# ir_board.net
KiCad netlist of a schematic drawn in EAGLE
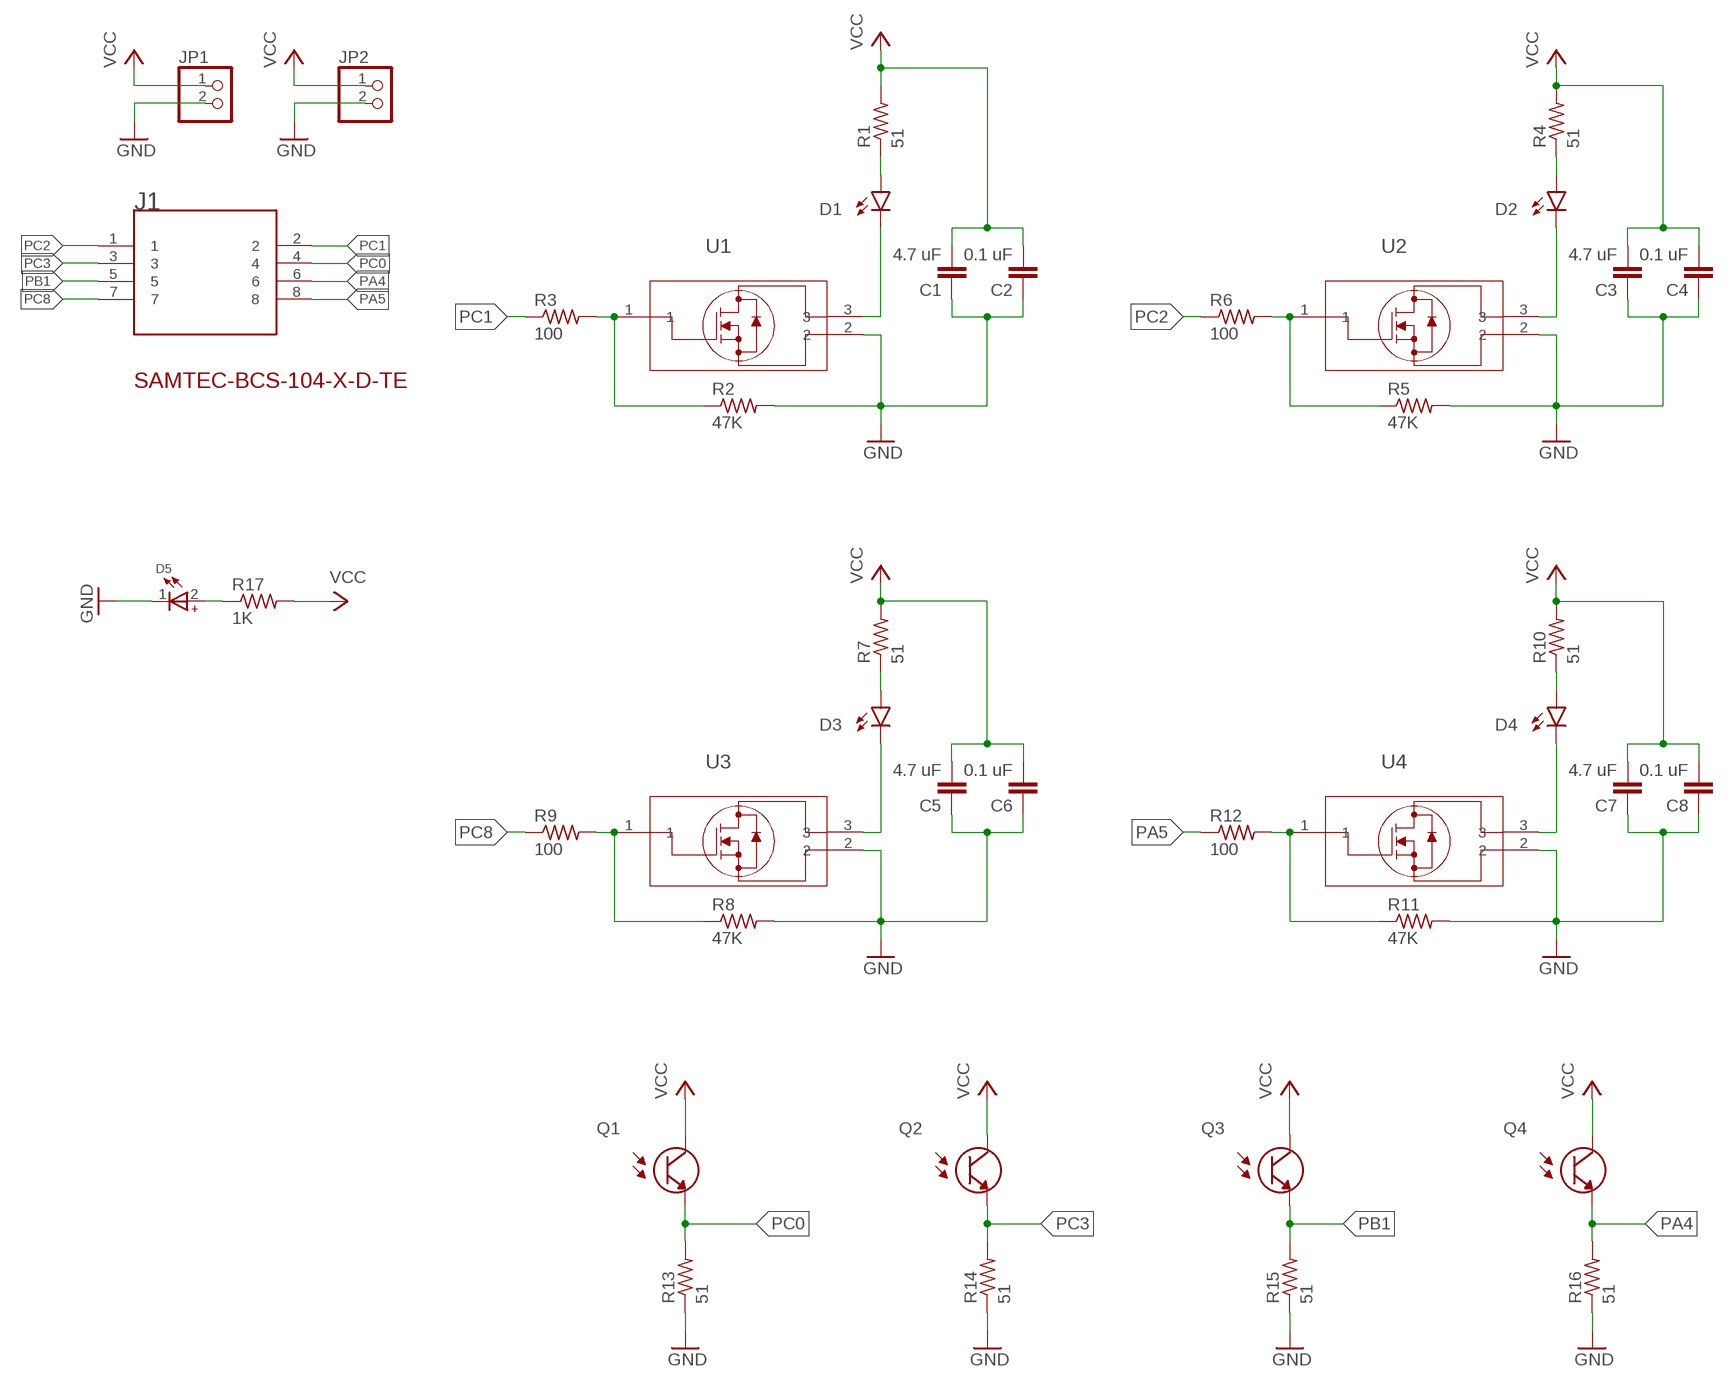
[diagram p0: schematic, sheet 1]

(export (version "E")
  (design (tool "Eeschema 10.0.6"))
  (components
    (comp (ref "C1")
      (value "4.7 uF")
      (footprint "eagle-import:C0805")
      (libsource (lib "eagle-import") (part "C-EUC0805"))
    )
    (comp (ref "C2")
      (value "0.1 uF")
      (footprint "eagle-import:C0805")
      (libsource (lib "eagle-import") (part "C-EUC0805"))
    )
    (comp (ref "C3")
      (value "4.7 uF")
      (footprint "eagle-import:C0805")
      (libsource (lib "eagle-import") (part "C-EUC0805"))
    )
    (comp (ref "C4")
      (value "0.1 uF")
      (footprint "eagle-import:C0805")
      (libsource (lib "eagle-import") (part "C-EUC0805"))
    )
    (comp (ref "C5")
      (value "4.7 uF")
      (footprint "eagle-import:C0805")
      (libsource (lib "eagle-import") (part "C-EUC0805"))
    )
    (comp (ref "C6")
      (value "0.1 uF")
      (footprint "eagle-import:C0805")
      (libsource (lib "eagle-import") (part "C-EUC0805"))
    )
    (comp (ref "C7")
      (value "4.7 uF")
      (footprint "eagle-import:C0805")
      (libsource (lib "eagle-import") (part "C-EUC0805"))
    )
    (comp (ref "C8")
      (value "0.1 uF")
      (footprint "eagle-import:C0805")
      (libsource (lib "eagle-import") (part "C-EUC0805"))
    )
    (comp (ref "D1")
      (value "LED5MM")
      (footprint "eagle-import:LED5MM")
      (libsource (lib "eagle-import") (part "LED5MM"))
    )
    (comp (ref "D2")
      (value "LED5MM")
      (footprint "eagle-import:LED5MM")
      (libsource (lib "eagle-import") (part "LED5MM"))
    )
    (comp (ref "D3")
      (value "LED5MM")
      (footprint "eagle-import:LED5MM")
      (libsource (lib "eagle-import") (part "LED5MM"))
    )
    (comp (ref "D4")
      (value "LED5MM")
      (footprint "eagle-import:LED5MM")
      (libsource (lib "eagle-import") (part "LED5MM"))
    )
    (comp (ref "D5")
      (value "WL-SMCW_0805_150080BS75000")
      (footprint "eagle-import:WL-SMCW_0805")
      (libsource (lib "eagle-import") (part "WL-SMCW_0805_150080BS75000"))
    )
    (comp (ref "J1")
      (value "SAMTEC-BCS-104-X-D-TEJ")
      (footprint "eagle-import:SAMTEC-BCS-104-X-D-TE")
      (fields (field (name "MF") "Samtec") (field (name "MP") "BCS-104-LM-D-TE"))
      (libsource (lib "eagle-import") (part "SAMTEC-BCS-104-X-D-TEJ"))
    )
    (comp (ref "JP1")
      (value "PINHD-1X2")
      (footprint "eagle-import:1X02")
      (libsource (lib "eagle-import") (part "PINHD-1X2"))
    )
    (comp (ref "JP2")
      (value "PINHD-1X2")
      (footprint "eagle-import:1X02")
      (libsource (lib "eagle-import") (part "PINHD-1X2"))
    )
    (comp (ref "Q1")
      (value "SFH_313_FA-3/4")
      (footprint "eagle-import:XDCR_SFH_313_FA-3_4")
      (fields (field (name "MF") "OSRAM Opto") (field (name "MP") "SFH 313 FA-3/4"))
      (libsource (lib "eagle-import") (part "SFH_313_FA-3/4"))
    )
    (comp (ref "Q2")
      (value "SFH_313_FA-3/4")
      (footprint "eagle-import:XDCR_SFH_313_FA-3_4")
      (fields (field (name "MF") "OSRAM Opto") (field (name "MP") "SFH 313 FA-3/4"))
      (libsource (lib "eagle-import") (part "SFH_313_FA-3/4"))
    )
    (comp (ref "Q3")
      (value "SFH_313_FA-3/4")
      (footprint "eagle-import:XDCR_SFH_313_FA-3_4")
      (fields (field (name "MF") "OSRAM Opto") (field (name "MP") "SFH 313 FA-3/4"))
      (libsource (lib "eagle-import") (part "SFH_313_FA-3/4"))
    )
    (comp (ref "Q4")
      (value "SFH_313_FA-3/4")
      (footprint "eagle-import:XDCR_SFH_313_FA-3_4")
      (fields (field (name "MF") "OSRAM Opto") (field (name "MP") "SFH 313 FA-3/4"))
      (libsource (lib "eagle-import") (part "SFH_313_FA-3/4"))
    )
    (comp (ref "R1")
      (value "51")
      (footprint "eagle-import:R0805")
      (libsource (lib "eagle-import") (part "R-US_R0805"))
    )
    (comp (ref "R2")
      (value "47K")
      (footprint "eagle-import:R0805")
      (libsource (lib "eagle-import") (part "R-US_R0805"))
    )
    (comp (ref "R3")
      (value "100")
      (footprint "eagle-import:R0805")
      (libsource (lib "eagle-import") (part "R-US_R0805"))
    )
    (comp (ref "R4")
      (value "51")
      (footprint "eagle-import:R0805")
      (libsource (lib "eagle-import") (part "R-US_R0805"))
    )
    (comp (ref "R5")
      (value "47K")
      (footprint "eagle-import:R0805")
      (libsource (lib "eagle-import") (part "R-US_R0805"))
    )
    (comp (ref "R6")
      (value "100")
      (footprint "eagle-import:R0805")
      (libsource (lib "eagle-import") (part "R-US_R0805"))
    )
    (comp (ref "R7")
      (value "51")
      (footprint "eagle-import:R0805")
      (libsource (lib "eagle-import") (part "R-US_R0805"))
    )
    (comp (ref "R8")
      (value "47K")
      (footprint "eagle-import:R0805")
      (libsource (lib "eagle-import") (part "R-US_R0805"))
    )
    (comp (ref "R9")
      (value "100")
      (footprint "eagle-import:R0805")
      (libsource (lib "eagle-import") (part "R-US_R0805"))
    )
    (comp (ref "R10")
      (value "51")
      (footprint "eagle-import:R0805")
      (libsource (lib "eagle-import") (part "R-US_R0805"))
    )
    (comp (ref "R11")
      (value "47K")
      (footprint "eagle-import:R0805")
      (libsource (lib "eagle-import") (part "R-US_R0805"))
    )
    (comp (ref "R12")
      (value "100")
      (footprint "eagle-import:R0805")
      (libsource (lib "eagle-import") (part "R-US_R0805"))
    )
    (comp (ref "R13")
      (value "51")
      (footprint "eagle-import:R0805")
      (libsource (lib "eagle-import") (part "R-US_R0805"))
    )
    (comp (ref "R14")
      (value "51")
      (footprint "eagle-import:R0805")
      (libsource (lib "eagle-import") (part "R-US_R0805"))
    )
    (comp (ref "R15")
      (value "51")
      (footprint "eagle-import:R0805")
      (libsource (lib "eagle-import") (part "R-US_R0805"))
    )
    (comp (ref "R16")
      (value "51")
      (footprint "eagle-import:R0805")
      (libsource (lib "eagle-import") (part "R-US_R0805"))
    )
    (comp (ref "R17")
      (value "1K")
      (footprint "eagle-import:R0805")
      (libsource (lib "eagle-import") (part "R-US_R0805"))
    )
    (comp (ref "U1")
      (value "2N7002LT1G")
      (footprint "eagle-import:SOT-23_3L_ONS")
      (fields (field (name "COPYRIGHT") "Copyright (C) 2018 Accelerated Designs. All rights reserved"))
      (libsource (lib "eagle-import") (part "2N7002LT1G"))
    )
    (comp (ref "U2")
      (value "2N7002LT1G")
      (footprint "eagle-import:SOT-23_3L_ONS")
      (fields (field (name "COPYRIGHT") "Copyright (C) 2018 Accelerated Designs. All rights reserved"))
      (libsource (lib "eagle-import") (part "2N7002LT1G"))
    )
    (comp (ref "U3")
      (value "2N7002LT1G")
      (footprint "eagle-import:SOT-23_3L_ONS")
      (fields (field (name "COPYRIGHT") "Copyright (C) 2018 Accelerated Designs. All rights reserved"))
      (libsource (lib "eagle-import") (part "2N7002LT1G"))
    )
    (comp (ref "U4")
      (value "2N7002LT1G")
      (footprint "eagle-import:SOT-23_3L_ONS")
      (fields (field (name "COPYRIGHT") "Copyright (C) 2018 Accelerated Designs. All rights reserved"))
      (libsource (lib "eagle-import") (part "2N7002LT1G"))
    )
  )
  (nets
    (net (code "1") (name "GND") (class "Default")
      (node (ref "C1") (pin "1") (pinfunction "1_1") (pintype "passive"))
      (node (ref "C2") (pin "1") (pinfunction "1_1") (pintype "passive"))
      (node (ref "C3") (pin "1") (pinfunction "1_1") (pintype "passive"))
      (node (ref "C4") (pin "1") (pinfunction "1_1") (pintype "passive"))
      (node (ref "C5") (pin "1") (pinfunction "1_1") (pintype "passive"))
      (node (ref "C6") (pin "1") (pinfunction "1_1") (pintype "passive"))
      (node (ref "C7") (pin "1") (pinfunction "1_1") (pintype "passive"))
      (node (ref "C8") (pin "1") (pinfunction "1_1") (pintype "passive"))
      (node (ref "D5") (pin "1") (pinfunction "-_1") (pintype "passive"))
      (node (ref "JP1") (pin "2") (pinfunction "2_2") (pintype "passive"))
      (node (ref "JP2") (pin "2") (pinfunction "2_2") (pintype "passive"))
      (node (ref "R11") (pin "2") (pinfunction "2_2") (pintype "passive"))
      (node (ref "R13") (pin "1") (pinfunction "1_1") (pintype "passive"))
      (node (ref "R14") (pin "1") (pinfunction "1_1") (pintype "passive"))
      (node (ref "R15") (pin "1") (pinfunction "1_1") (pintype "passive"))
      (node (ref "R16") (pin "1") (pinfunction "1_1") (pintype "passive"))
      (node (ref "R2") (pin "2") (pinfunction "2_2") (pintype "passive"))
      (node (ref "R5") (pin "2") (pinfunction "2_2") (pintype "passive"))
      (node (ref "R8") (pin "2") (pinfunction "2_2") (pintype "passive"))
      (node (ref "U1") (pin "2") (pinfunction "2_2") (pintype "passive"))
      (node (ref "U2") (pin "2") (pinfunction "2_2") (pintype "passive"))
      (node (ref "U3") (pin "2") (pinfunction "2_2") (pintype "passive"))
      (node (ref "U4") (pin "2") (pinfunction "2_2") (pintype "passive"))
    )
    (net (code "2") (name "Net-(D1-C)") (class "Default")
      (node (ref "D1") (pin "K") (pinfunction "C_K") (pintype "passive"))
      (node (ref "U1") (pin "3") (pinfunction "3_3") (pintype "passive"))
    )
    (net (code "3") (name "Net-(D1-PadA)") (class "Default")
      (node (ref "D1") (pin "A") (pinfunction "A_A") (pintype "passive"))
      (node (ref "R1") (pin "1") (pinfunction "1_1") (pintype "passive"))
    )
    (net (code "4") (name "Net-(D2-C)") (class "Default")
      (node (ref "D2") (pin "K") (pinfunction "C_K") (pintype "passive"))
      (node (ref "U2") (pin "3") (pinfunction "3_3") (pintype "passive"))
    )
    (net (code "5") (name "Net-(D2-PadA)") (class "Default")
      (node (ref "D2") (pin "A") (pinfunction "A_A") (pintype "passive"))
      (node (ref "R4") (pin "1") (pinfunction "1_1") (pintype "passive"))
    )
    (net (code "6") (name "Net-(D3-C)") (class "Default")
      (node (ref "D3") (pin "K") (pinfunction "C_K") (pintype "passive"))
      (node (ref "U3") (pin "3") (pinfunction "3_3") (pintype "passive"))
    )
    (net (code "7") (name "Net-(D3-PadA)") (class "Default")
      (node (ref "D3") (pin "A") (pinfunction "A_A") (pintype "passive"))
      (node (ref "R7") (pin "1") (pinfunction "1_1") (pintype "passive"))
    )
    (net (code "8") (name "Net-(D4-C)") (class "Default")
      (node (ref "D4") (pin "K") (pinfunction "C_K") (pintype "passive"))
      (node (ref "U4") (pin "3") (pinfunction "3_3") (pintype "passive"))
    )
    (net (code "9") (name "Net-(D4-PadA)") (class "Default")
      (node (ref "D4") (pin "A") (pinfunction "A_A") (pintype "passive"))
      (node (ref "R10") (pin "1") (pinfunction "1_1") (pintype "passive"))
    )
    (net (code "10") (name "Net-(D5-+)") (class "Default")
      (node (ref "D5") (pin "2") (pinfunction "+_2") (pintype "passive"))
      (node (ref "R17") (pin "1") (pinfunction "1_1") (pintype "passive"))
    )
    (net (code "11") (name "Net-(R2-Pad1)") (class "Default")
      (node (ref "R2") (pin "1") (pinfunction "1_1") (pintype "passive"))
      (node (ref "R3") (pin "2") (pinfunction "2_2") (pintype "passive"))
      (node (ref "U1") (pin "1") (pinfunction "1_1") (pintype "passive"))
    )
    (net (code "12") (name "Net-(R5-Pad1)") (class "Default")
      (node (ref "R5") (pin "1") (pinfunction "1_1") (pintype "passive"))
      (node (ref "R6") (pin "2") (pinfunction "2_2") (pintype "passive"))
      (node (ref "U2") (pin "1") (pinfunction "1_1") (pintype "passive"))
    )
    (net (code "13") (name "Net-(R8-Pad1)") (class "Default")
      (node (ref "R8") (pin "1") (pinfunction "1_1") (pintype "passive"))
      (node (ref "R9") (pin "2") (pinfunction "2_2") (pintype "passive"))
      (node (ref "U3") (pin "1") (pinfunction "1_1") (pintype "passive"))
    )
    (net (code "14") (name "Net-(R11-Pad1)") (class "Default")
      (node (ref "R11") (pin "1") (pinfunction "1_1") (pintype "passive"))
      (node (ref "R12") (pin "2") (pinfunction "2_2") (pintype "passive"))
      (node (ref "U4") (pin "1") (pinfunction "1_1") (pintype "passive"))
    )
    (net (code "15") (name "PA4") (class "Default")
      (node (ref "J1") (pin "6") (pinfunction "6_6") (pintype "passive"))
      (node (ref "Q4") (pin "1") (pinfunction "E_1") (pintype "passive"))
      (node (ref "R16") (pin "2") (pinfunction "2_2") (pintype "passive"))
    )
    (net (code "16") (name "PA5") (class "Default")
      (node (ref "J1") (pin "8") (pinfunction "8_8") (pintype "passive"))
      (node (ref "R12") (pin "1") (pinfunction "1_1") (pintype "passive"))
    )
    (net (code "17") (name "PB1") (class "Default")
      (node (ref "J1") (pin "5") (pinfunction "5_5") (pintype "passive"))
      (node (ref "Q3") (pin "1") (pinfunction "E_1") (pintype "passive"))
      (node (ref "R15") (pin "2") (pinfunction "2_2") (pintype "passive"))
    )
    (net (code "18") (name "PC0") (class "Default")
      (node (ref "J1") (pin "4") (pinfunction "4_4") (pintype "passive"))
      (node (ref "Q1") (pin "1") (pinfunction "E_1") (pintype "passive"))
      (node (ref "R13") (pin "2") (pinfunction "2_2") (pintype "passive"))
    )
    (net (code "19") (name "PC1") (class "Default")
      (node (ref "J1") (pin "2") (pinfunction "2_2") (pintype "passive"))
      (node (ref "R3") (pin "1") (pinfunction "1_1") (pintype "passive"))
    )
    (net (code "20") (name "PC2") (class "Default")
      (node (ref "J1") (pin "1") (pinfunction "1_1") (pintype "passive"))
      (node (ref "R6") (pin "1") (pinfunction "1_1") (pintype "passive"))
    )
    (net (code "21") (name "PC3") (class "Default")
      (node (ref "J1") (pin "3") (pinfunction "3_3") (pintype "passive"))
      (node (ref "Q2") (pin "1") (pinfunction "E_1") (pintype "passive"))
      (node (ref "R14") (pin "2") (pinfunction "2_2") (pintype "passive"))
    )
    (net (code "22") (name "PC8") (class "Default")
      (node (ref "J1") (pin "7") (pinfunction "7_7") (pintype "passive"))
      (node (ref "R9") (pin "1") (pinfunction "1_1") (pintype "passive"))
    )
    (net (code "23") (name "VCC") (class "Default")
      (node (ref "C1") (pin "2") (pinfunction "2_2") (pintype "passive"))
      (node (ref "C2") (pin "2") (pinfunction "2_2") (pintype "passive"))
      (node (ref "C3") (pin "2") (pinfunction "2_2") (pintype "passive"))
      (node (ref "C4") (pin "2") (pinfunction "2_2") (pintype "passive"))
      (node (ref "C5") (pin "2") (pinfunction "2_2") (pintype "passive"))
      (node (ref "C6") (pin "2") (pinfunction "2_2") (pintype "passive"))
      (node (ref "C7") (pin "2") (pinfunction "2_2") (pintype "passive"))
      (node (ref "C8") (pin "2") (pinfunction "2_2") (pintype "passive"))
      (node (ref "JP1") (pin "1") (pinfunction "1_1") (pintype "passive"))
      (node (ref "JP2") (pin "1") (pinfunction "1_1") (pintype "passive"))
      (node (ref "Q1") (pin "2") (pinfunction "C_2") (pintype "passive"))
      (node (ref "Q2") (pin "2") (pinfunction "C_2") (pintype "passive"))
      (node (ref "Q3") (pin "2") (pinfunction "C_2") (pintype "passive"))
      (node (ref "Q4") (pin "2") (pinfunction "C_2") (pintype "passive"))
      (node (ref "R1") (pin "2") (pinfunction "2_2") (pintype "passive"))
      (node (ref "R10") (pin "2") (pinfunction "2_2") (pintype "passive"))
      (node (ref "R17") (pin "2") (pinfunction "2_2") (pintype "passive"))
      (node (ref "R4") (pin "2") (pinfunction "2_2") (pintype "passive"))
      (node (ref "R7") (pin "2") (pinfunction "2_2") (pintype "passive"))
    )
  )
)
